# LOKI-HBS-V1-r2_0.net
KiCad netlist of a schematic drawn in Altium Designer
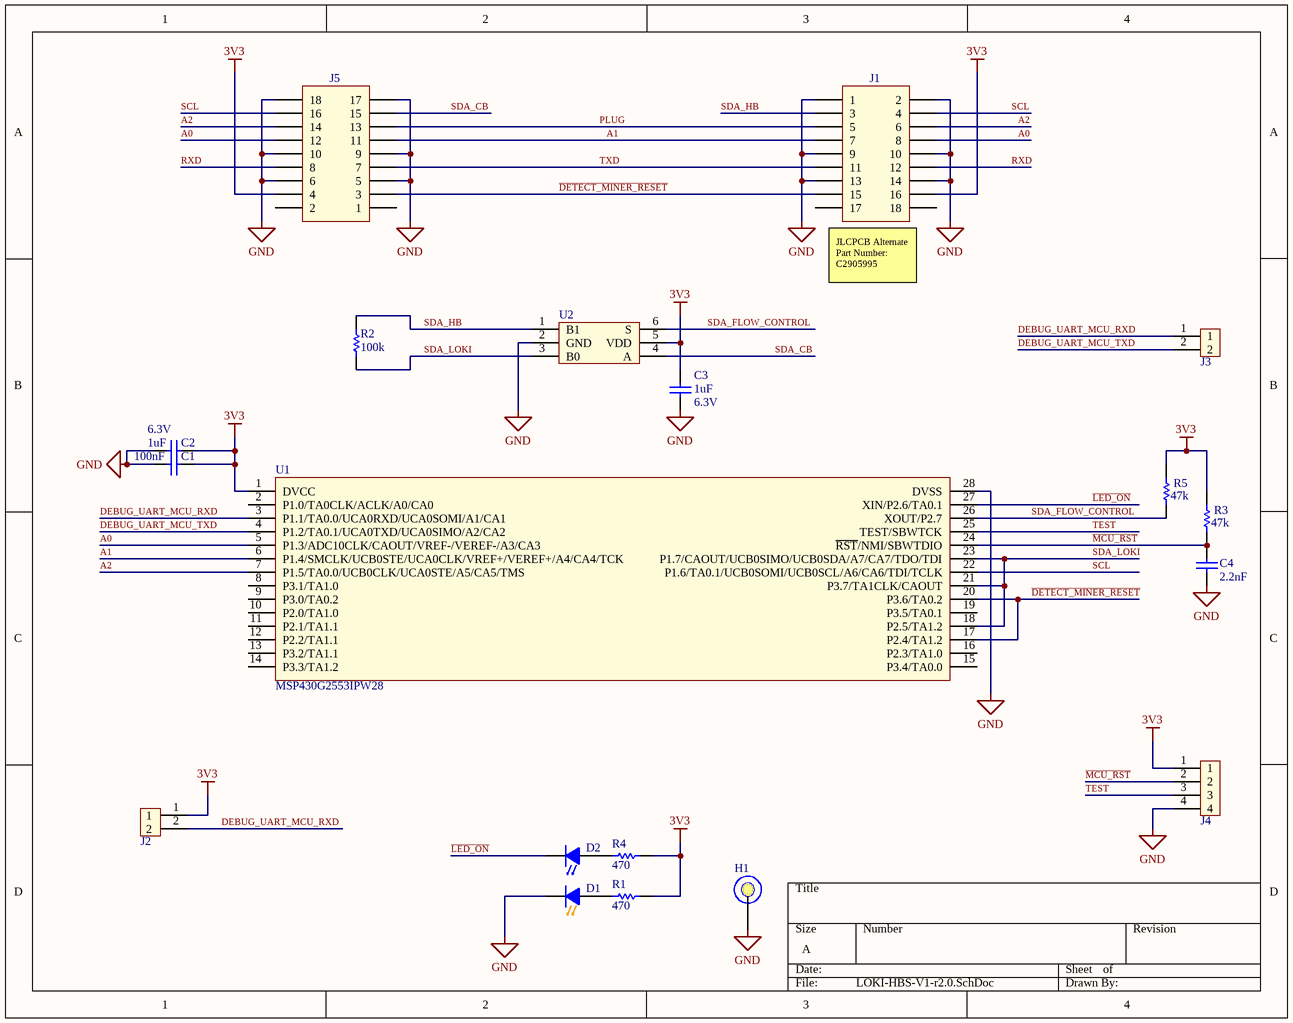
[diagram p0: LOKI-HBS-V1-r2.0.SchDoc]

(export (version "E")
  (design (tool "Eeschema 10.0.6"))
  (components
    (comp (ref "C1")
      (value "100nF")
      (footprint "C0402_L")
      (description "CAP CER 0.1UF 10V X5R 0402")
      (fields
        (field (name "PART NUMBER") "C1005X5R1A104K050BA (2)")
        (field (name "MANUFACTURER") "TDK Corporation")
      )
      (libsource (lib "RS_General_LIB") (part "Cnonpol"))
    )
    (comp (ref "C2")
      (value "1uF")
      (footprint "C0402_L")
      (description "CAP CER 1UF 6.3V X5R 0402")
      (fields
        (field (name "PART NUMBER") "JMK105BJ105KV-F")
        (field (name "MANUFACTURER") "Taiyo Yuden")
        (field (name "VOLTAGE - RATED") "6.3V")
      )
      (libsource (lib "RS_General_LIB") (part "Cnonpol"))
    )
    (comp (ref "C3")
      (value "1uF")
      (footprint "C0402_L")
      (description "CAP CER 1UF 6.3V X5R 0402")
      (fields
        (field (name "PART NUMBER") "JMK105BJ105KV-F")
        (field (name "MANUFACTURER") "Taiyo Yuden")
        (field (name "VOLTAGE - RATED") "6.3V")
      )
      (libsource (lib "RS_General_LIB") (part "Cnonpol"))
    )
    (comp (ref "C4")
      (value "2.2nF")
      (footprint "C0402_L")
      (description "CAP CER 2200PF 50V 10% X7R 0402")
      (fields
        (field (name "PART NUMBER") "GRM155R71H222KA01D")
        (field (name "MANUFACTURER") "Murata Electronics North America")
      )
      (libsource (lib "RS_General_LIB") (part "C6"))
    )
    (comp (ref "D1")
      (value "LED-ORANGE")
      (footprint "LED0603_L_ORANGE")
      (description "Led Orange Clear 1608 SMD")
      (fields (field (name "PART NUMBER") "B1931UD--05D000314U1930") (field (name "MANUFACTURER") "Inolux"))
      (libsource (lib "RS_General_LIB") (part "LED-ORANGE"))
    )
    (comp (ref "D2")
      (value "LED-BLUE")
      (footprint "LED0603_L_BLUE")
      (description "Single Color LED, Ultra Bright Blue, Water Clear, 1.1mm")
      (fields (field (name "PART NUMBER") "LTST-C191TBKT") (field (name "MANUFACTURER") "Vishay Lite-On"))
      (libsource (lib "RS_General_LIB") (part "LED-BLUE"))
    )
    (comp (ref "H1")
      (value "GenericConnectedMountingHole")
      (footprint "MountingHole(3mm hole, 4.5mm pad)")
      (description "3mm mounting hole with 4.5mm pad")
      (fields (field (name "PART NUMBER") "MountingHole(3mm hole, 4.5mm pad)"))
      (libsource (lib "RS_General_LIB") (part "GenericConnectedMountingHole"))
    )
    (comp (ref "J1")
      (value "HEADER_18POS_2x9")
      (footprint "BF050-18")
      (description "18POS, 2MM Pitch Pin Hdr, Dil, T")
      (fields
        (field (name "PART NUMBER") "BF050-18-A-B-0400-0300-L-G")
        (field (name "MANUFACTURER") "Global Connector Technology")
      )
      (libsource (lib "") (part "HEADER_18POS_2x9_1"))
    )
    (comp (ref "J2")
      (value "Header_2POS")
      (footprint "2POS_RA_TH")
      (description "Conn Unshrouded Header HDR 2 POS 2.54mm Solder RA Thru-Hole")
      (fields (field (name "PART NUMBER") "PH1RB-02-UA") (field (name "MANUFACTURER") "Adam Equipment"))
      (libsource (lib "RS_General_LIB") (part "Header_2POS"))
    )
    (comp (ref "J3")
      (value "Header_2POS")
      (footprint "H2_2.54mm_S_THOLE")
      (description "Conn Unshrouded Header HDR 2 POS 2.54mm Solder S Thru-Hole")
      (fields (field (name "PART NUMBER") "TSW-106-08-L-S-R"))
      (libsource (lib "") (part "Header_2POS_1"))
    )
    (comp (ref "J4")
      (value "Header_4POS")
      (footprint "H4_2.54mm_S_THOLE")
      (description "Conn Header Vert 2POS 2.54MM")
      (fields (field (name "PART NUMBER") "PRPC002SAAN-RC") (field (name "MANUFACTURER") "Sullins"))
      (libsource (lib "RS_General_LIB") (part "Header_4POS"))
    )
    (comp (ref "J5")
      (value "HEADER_18POS_2x9")
      (footprint "2145-2X09")
      (description "18 Position Socket Connector 0.079\" (2.00mm) Through Hole Gold")
      (fields (field (name "PART NUMBER") "2145-2X09") (field (name "MANUFACTURER") "Oupiin"))
      (libsource (lib "RS_General_LIB") (part "HEADER_18POS_2x9"))
    )
    (comp (ref "R1")
      (value "470")
      (footprint "R0402_L")
      (description "RES 470 OHM 1/10W 1% 0402 SMD")
      (fields (field (name "PART NUMBER") "ERJ-2RKF4700X") (field (name "MANUFACTURER") "Panasonic - ECG"))
      (libsource (lib "RS_General_LIB") (part "R8"))
    )
    (comp (ref "R2")
      (value "100k")
      (footprint "R0402_L")
      (description "RES SMD 100K OHM 1% 1/16W 0402")
      (fields (field (name "PART NUMBER") "CRCW0402100KFKED") (field (name "OWLET PART NUMBER") "12.0037.00"))
      (libsource (lib "RS_General_LIB") (part "Rgeneric"))
    )
    (comp (ref "R3")
      (value "47k")
      (footprint "R0402_L")
      (description "RES 47K OHM 1/10W 5% 0402 SMD")
      (fields
        (field (name "MANUFACTURER") "Panasonic Electronic Components")
        (field (name "MANUFACTURER PART NUMBER") "ERJ-2GEJ473X")
      )
      (libsource (lib "RS_General_LIB") (part "R52"))
    )
    (comp (ref "R4")
      (value "470")
      (footprint "R0402_L")
      (description "RES 470 OHM 1/10W 1% 0402 SMD")
      (fields (field (name "PART NUMBER") "ERJ-2RKF4700X") (field (name "MANUFACTURER") "Panasonic - ECG"))
      (libsource (lib "RS_General_LIB") (part "R8"))
    )
    (comp (ref "R5")
      (value "47k")
      (footprint "R0402_L")
      (description "RES 47K OHM 1/10W 5% 0402 SMD")
      (fields
        (field (name "MANUFACTURER") "Panasonic Electronic Components")
        (field (name "MANUFACTURER PART NUMBER") "ERJ-2GEJ473X")
      )
      (libsource (lib "RS_General_LIB") (part "R52"))
    )
    (comp (ref "U1")
      (value "MSP430G2553IPW28")
      (footprint "28-TSSOP_L")
      (description "MSP430 MSP430G2xx Microcontroller IC 16-Bit 16MHz 16KB (16K x 8) FLASH 28-TSSOP")
      (fields
        (field (name "PART NUMBER") "MSP430G2553IPW28R")
        (field (name "MANUFACTURER") "Texas Instruments")
      )
      (libsource (lib "RS_General_LIB") (part "MSP430G2553IPW28"))
    )
    (comp (ref "U2")
      (value "PI5A3157CEX")
      (footprint "SC70-6")
      (description "Analogue Sw, Spdt, -40 To 85Deg C Rohs Compliant: Yes")
      (fields (field (name "MANUFACTURER") "Diodes"))
      (libsource (lib "RS_General_LIB") (part "PI5A3157CEX"))
    )
  )
  (nets
    (net (code "1") (name "/A0") (class "Default")
      (node (ref "J1") (pin "8") (pinfunction "8_8") (pintype "passive"))
      (node (ref "J5") (pin "12") (pinfunction "12_12") (pintype "passive"))
      (node (ref "U1") (pin "5") (pinfunction "P1.3/ADC10CLK/CAOUT/VREF-/VEREF-/A3/CA3_5") (pintype "passive"))
    )
    (net (code "2") (name "/A1") (class "Default")
      (node (ref "J1") (pin "7") (pinfunction "7_7") (pintype "passive"))
      (node (ref "J5") (pin "11") (pinfunction "11_11") (pintype "passive"))
      (node (ref "U1") (pin "6") (pinfunction "P1.4/SMCLK/UCB0STE/UCA0CLK/VREF+/VEREF+/A4/CA4/TCK_6") (pintype "passive"))
    )
    (net (code "3") (name "/A2") (class "Default")
      (node (ref "J1") (pin "6") (pinfunction "6_6") (pintype "passive"))
      (node (ref "J5") (pin "14") (pinfunction "14_14") (pintype "passive"))
      (node (ref "U1") (pin "7") (pinfunction "P1.5/TA0.0/UCB0CLK/UCA0STE/A5/CA5/TMS_7") (pintype "passive"))
    )
    (net (code "4") (name "/DEBUG_UART_MCU_RXD") (class "Default")
      (node (ref "J2") (pin "2") (pinfunction "2_2") (pintype "passive"))
      (node (ref "J3") (pin "1") (pinfunction "1_1") (pintype "passive"))
      (node (ref "U1") (pin "3") (pinfunction "P1.1/TA0.0/UCA0RXD/UCA0SOMI/A1/CA1_3") (pintype "passive"))
    )
    (net (code "5") (name "/DEBUG_UART_MCU_TXD") (class "Default")
      (node (ref "J3") (pin "2") (pinfunction "2_2") (pintype "passive"))
      (node (ref "U1") (pin "4") (pinfunction "P1.2/TA0.1/UCA0TXD/UCA0SIMO/A2/CA2_4") (pintype "passive"))
    )
    (net (code "6") (name "/PLUG") (class "Default")
      (node (ref "J1") (pin "5") (pinfunction "5_5") (pintype "passive"))
      (node (ref "J5") (pin "13") (pinfunction "13_13") (pintype "passive"))
    )
    (net (code "7") (name "/RXD") (class "Default")
      (node (ref "J1") (pin "12") (pinfunction "12_12") (pintype "passive"))
      (node (ref "J5") (pin "8") (pinfunction "8_8") (pintype "passive"))
    )
    (net (code "8") (name "/SCL") (class "Default")
      (node (ref "J1") (pin "4") (pinfunction "4_4") (pintype "passive"))
      (node (ref "J5") (pin "16") (pinfunction "16_16") (pintype "passive"))
      (node (ref "U1") (pin "22") (pinfunction "P1.6/TA0.1/UCB0SOMI/UCB0SCL/A6/CA6/TDI/TCLK_22") (pintype "passive"))
    )
    (net (code "9") (name "/SDA_CB") (class "Default")
      (node (ref "J5") (pin "15") (pinfunction "15_15") (pintype "passive"))
      (node (ref "U2") (pin "4") (pinfunction "A_4") (pintype "passive"))
    )
    (net (code "10") (name "/SDA_FLOW_CONTROL") (class "Default")
      (node (ref "R5") (pin "1") (pinfunction "1_1") (pintype "passive"))
      (node (ref "U1") (pin "26") (pinfunction "XOUT/P2.7_26") (pintype "passive"))
      (node (ref "U2") (pin "6") (pinfunction "S_6") (pintype "passive"))
    )
    (net (code "11") (name "/SDA_HB") (class "Default")
      (node (ref "J1") (pin "3") (pinfunction "3_3") (pintype "passive"))
      (node (ref "R2") (pin "2") (pinfunction "2_2") (pintype "passive"))
      (node (ref "U2") (pin "1") (pinfunction "B1_1") (pintype "passive"))
    )
    (net (code "12") (name "/SDA_LOKI") (class "Default")
      (node (ref "R2") (pin "1") (pinfunction "1_1") (pintype "passive"))
      (node (ref "U1") (pin "18") (pinfunction "P2.5/TA1.2_18") (pintype "passive"))
      (node (ref "U1") (pin "21") (pinfunction "P3.7/TA1CLK/CAOUT_21") (pintype "passive"))
      (node (ref "U1") (pin "23") (pinfunction "P1.7/CAOUT/UCB0SIMO/UCB0SDA/A7/CA7/TDO/TDI_23") (pintype "passive"))
      (node (ref "U2") (pin "3") (pinfunction "B0_3") (pintype "passive"))
    )
    (net (code "13") (name "/TEST") (class "Default")
      (node (ref "J4") (pin "3") (pinfunction "3_3") (pintype "passive"))
      (node (ref "U1") (pin "25") (pinfunction "TEST/SBWTCK_25") (pintype "passive"))
    )
    (net (code "14") (name "/TXD") (class "Default")
      (node (ref "J1") (pin "11") (pinfunction "11_11") (pintype "passive"))
      (node (ref "J5") (pin "7") (pinfunction "7_7") (pintype "passive"))
    )
    (net (code "15") (name "/~{DETECT_MINER_RESET}") (class "Default")
      (node (ref "J1") (pin "15") (pinfunction "15_15") (pintype "passive"))
      (node (ref "J5") (pin "3") (pinfunction "3_3") (pintype "passive"))
      (node (ref "U1") (pin "17") (pinfunction "P2.4/TA1.2_17") (pintype "passive"))
      (node (ref "U1") (pin "20") (pinfunction "P3.6/TA0.2_20") (pintype "passive"))
    )
    (net (code "16") (name "/~{LED_ON}") (class "Default")
      (node (ref "D2") (pin "2") (pinfunction "K_2") (pintype "passive"))
      (node (ref "U1") (pin "27") (pinfunction "XIN/P2.6/TA0.1_27") (pintype "passive"))
    )
    (net (code "17") (name "/~{MCU_RST}") (class "Default")
      (node (ref "C4") (pin "2") (pinfunction "2_2") (pintype "passive"))
      (node (ref "J4") (pin "2") (pinfunction "2_2") (pintype "passive"))
      (node (ref "R3") (pin "1") (pinfunction "1_1") (pintype "passive"))
      (node (ref "U1") (pin "24") (pinfunction "~{RST}/NMI/SBWTDIO_24") (pintype "passive"))
    )
    (net (code "18") (name "3V3") (class "Default")
      (node (ref "C1") (pin "2") (pinfunction "2_2") (pintype "passive"))
      (node (ref "C2") (pin "2") (pinfunction "2_2") (pintype "passive"))
      (node (ref "C3") (pin "2") (pinfunction "2_2") (pintype "passive"))
      (node (ref "J1") (pin "16") (pinfunction "16_16") (pintype "passive"))
      (node (ref "J2") (pin "1") (pinfunction "1_1") (pintype "passive"))
      (node (ref "J4") (pin "1") (pinfunction "1_1") (pintype "passive"))
      (node (ref "J5") (pin "4") (pinfunction "4_4") (pintype "passive"))
      (node (ref "R1") (pin "2") (pinfunction "2_2") (pintype "passive"))
      (node (ref "R3") (pin "2") (pinfunction "2_2") (pintype "passive"))
      (node (ref "R4") (pin "2") (pinfunction "2_2") (pintype "passive"))
      (node (ref "R5") (pin "2") (pinfunction "2_2") (pintype "passive"))
      (node (ref "U1") (pin "1") (pinfunction "DVCC_1") (pintype "passive"))
      (node (ref "U2") (pin "5") (pinfunction "VDD_5") (pintype "passive"))
    )
    (net (code "19") (name "GND") (class "Default")
      (node (ref "C1") (pin "1") (pinfunction "1_1") (pintype "passive"))
      (node (ref "C2") (pin "1") (pinfunction "1_1") (pintype "passive"))
      (node (ref "C3") (pin "1") (pinfunction "1_1") (pintype "passive"))
      (node (ref "C4") (pin "1") (pinfunction "1_1") (pintype "passive"))
      (node (ref "D1") (pin "2") (pinfunction "K_2") (pintype "passive"))
      (node (ref "H1") (pin "1") (pinfunction "0_1") (pintype "passive"))
      (node (ref "J1") (pin "1") (pinfunction "1_1") (pintype "passive"))
      (node (ref "J1") (pin "10") (pinfunction "10_10") (pintype "passive"))
      (node (ref "J1") (pin "13") (pinfunction "13_13") (pintype "passive"))
      (node (ref "J1") (pin "14") (pinfunction "14_14") (pintype "passive"))
      (node (ref "J1") (pin "2") (pinfunction "2_2") (pintype "passive"))
      (node (ref "J1") (pin "9") (pinfunction "9_9") (pintype "passive"))
      (node (ref "J4") (pin "4") (pinfunction "4_4") (pintype "passive"))
      (node (ref "J5") (pin "10") (pinfunction "10_10") (pintype "passive"))
      (node (ref "J5") (pin "17") (pinfunction "17_17") (pintype "passive"))
      (node (ref "J5") (pin "18") (pinfunction "18_18") (pintype "passive"))
      (node (ref "J5") (pin "5") (pinfunction "5_5") (pintype "passive"))
      (node (ref "J5") (pin "6") (pinfunction "6_6") (pintype "passive"))
      (node (ref "J5") (pin "9") (pinfunction "9_9") (pintype "passive"))
      (node (ref "U1") (pin "28") (pinfunction "DVSS_28") (pintype "passive"))
      (node (ref "U2") (pin "2") (pinfunction "GND_2") (pintype "passive"))
    )
    (net (code "20") (name "Net-(D1-A)") (class "Default")
      (node (ref "D1") (pin "1") (pinfunction "A_1") (pintype "passive"))
      (node (ref "R1") (pin "1") (pinfunction "1_1") (pintype "passive"))
    )
    (net (code "21") (name "Net-(D2-A)") (class "Default")
      (node (ref "D2") (pin "1") (pinfunction "A_1") (pintype "passive"))
      (node (ref "R4") (pin "1") (pinfunction "1_1") (pintype "passive"))
    )
    (net (code "22") (name "unconnected-(J1-Pad17)") (class "Default")
      (node (ref "J1") (pin "17") (pinfunction "17_17") (pintype "passive"))
    )
    (net (code "23") (name "unconnected-(J1-Pad18)") (class "Default")
      (node (ref "J1") (pin "18") (pinfunction "18_18") (pintype "passive"))
    )
    (net (code "24") (name "unconnected-(J5-Pad1)") (class "Default")
      (node (ref "J5") (pin "1") (pinfunction "1_1") (pintype "passive"))
    )
    (net (code "25") (name "unconnected-(J5-Pad2)") (class "Default")
      (node (ref "J5") (pin "2") (pinfunction "2_2") (pintype "passive"))
    )
    (net (code "26") (name "unconnected-(U1-P1.0{slash}TA0CLK{slash}ACLK{slash}A0{slash}CA0-Pad2)") (class "Default")
      (node (ref "U1") (pin "2") (pinfunction "P1.0/TA0CLK/ACLK/A0/CA0_2") (pintype "passive"))
    )
    (net (code "27") (name "unconnected-(U1-P2.0{slash}TA1.0-Pad10)") (class "Default")
      (node (ref "U1") (pin "10") (pinfunction "P2.0/TA1.0_10") (pintype "passive"))
    )
    (net (code "28") (name "unconnected-(U1-P2.1{slash}TA1.1-Pad11)") (class "Default")
      (node (ref "U1") (pin "11") (pinfunction "P2.1/TA1.1_11") (pintype "passive"))
    )
    (net (code "29") (name "unconnected-(U1-P2.2{slash}TA1.1-Pad12)") (class "Default")
      (node (ref "U1") (pin "12") (pinfunction "P2.2/TA1.1_12") (pintype "passive"))
    )
    (net (code "30") (name "unconnected-(U1-P2.3{slash}TA1.0-Pad16)") (class "Default")
      (node (ref "U1") (pin "16") (pinfunction "P2.3/TA1.0_16") (pintype "passive"))
    )
    (net (code "31") (name "unconnected-(U1-P3.0{slash}TA0.2-Pad9)") (class "Default")
      (node (ref "U1") (pin "9") (pinfunction "P3.0/TA0.2_9") (pintype "passive"))
    )
    (net (code "32") (name "unconnected-(U1-P3.1{slash}TA1.0-Pad8)") (class "Default")
      (node (ref "U1") (pin "8") (pinfunction "P3.1/TA1.0_8") (pintype "passive"))
    )
    (net (code "33") (name "unconnected-(U1-P3.2{slash}TA1.1-Pad13)") (class "Default")
      (node (ref "U1") (pin "13") (pinfunction "P3.2/TA1.1_13") (pintype "passive"))
    )
    (net (code "34") (name "unconnected-(U1-P3.3{slash}TA1.2-Pad14)") (class "Default")
      (node (ref "U1") (pin "14") (pinfunction "P3.3/TA1.2_14") (pintype "passive"))
    )
    (net (code "35") (name "unconnected-(U1-P3.4{slash}TA0.0-Pad15)") (class "Default")
      (node (ref "U1") (pin "15") (pinfunction "P3.4/TA0.0_15") (pintype "passive"))
    )
    (net (code "36") (name "unconnected-(U1-P3.5{slash}TA0.1-Pad19)") (class "Default")
      (node (ref "U1") (pin "19") (pinfunction "P3.5/TA0.1_19") (pintype "passive"))
    )
  )
)
